# fpgaConfig.net
KiCad netlist of a schematic drawn in Altium Designer
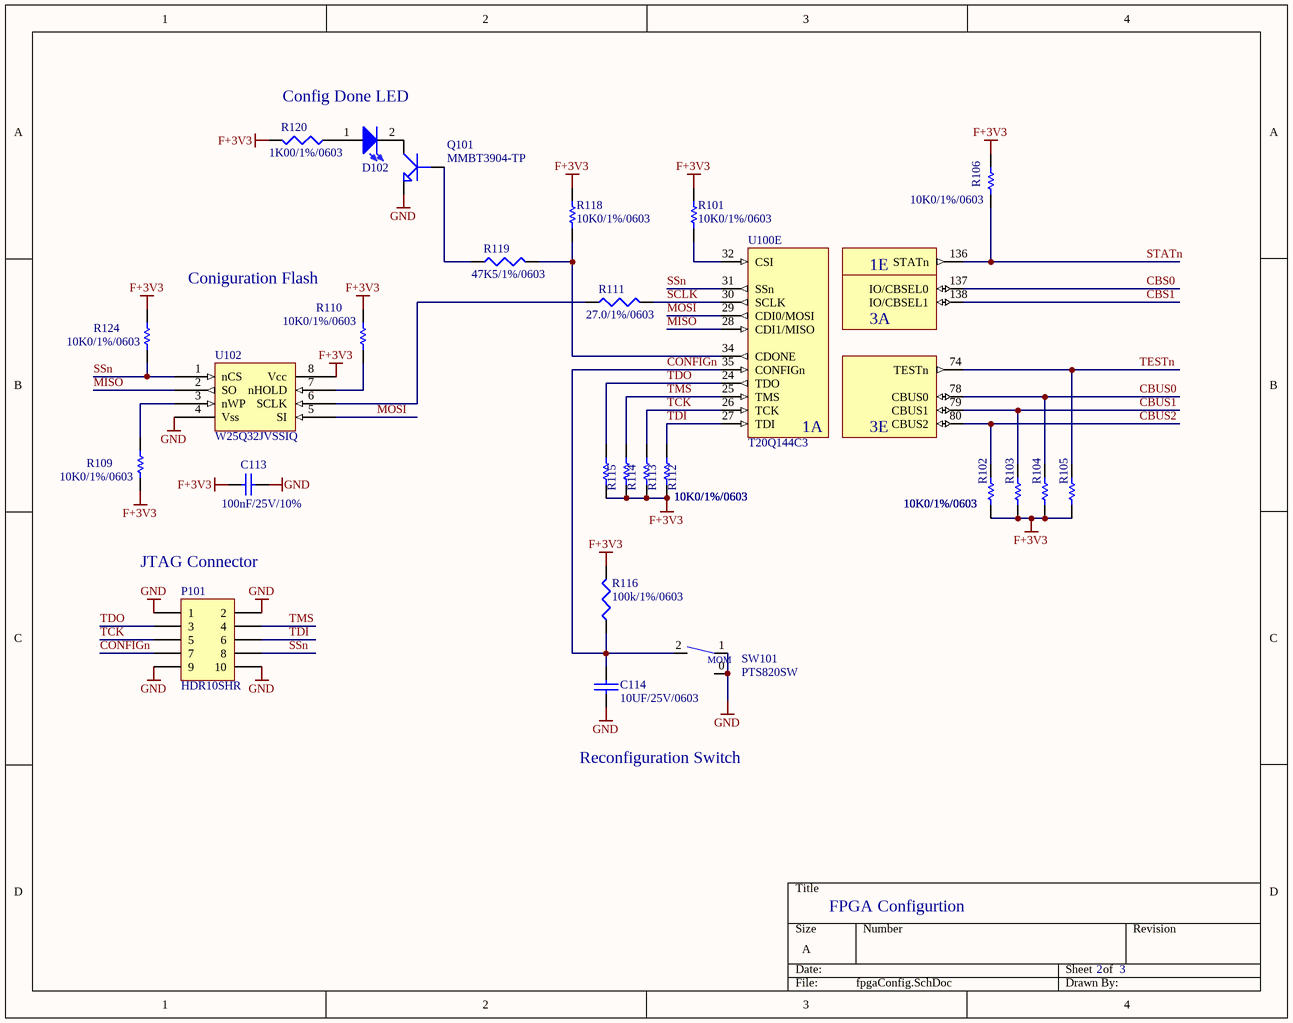
[diagram p0: fpgaConfig.SchDoc]

(export (version "E")
  (design (tool "Eeschema 10.0.6"))
  (components
    (comp (ref "C113")
      (value "100nF/25V/10%")
      (footprint "MY0603")
      (description "0.1µF ±10% 25V Ceramic Capacitor X7R 0603 (1608 Metric)")
      (fields (field (name "MFG") "AVX"))
      (libsource (lib "Capacitors") (part "CAP100NF25V"))
    )
    (comp (ref "C114")
      (value "10UF/25V/0603")
      (footprint "0603")
      (description "10 µF ±20% 25V Ceramic Capacitor X5R 0603 (1608 Metric)")
      (fields (field (name "MFG") "Samsung"))
      (libsource (lib "Capacitors") (part "10UF/25V/0603"))
    )
    (comp (ref "D102")
      (value "LTST-C191KGKT")
      (footprint "LED0603")
      (description "Green 571nm LED Indication - Discrete 2V 0603 (1608 Metric)")
      (fields (field (name "MFG") "Liteon"))
      (libsource (lib "MiscSemi") (part "LTST-C191KGKT"))
    )
    (comp (ref "P101")
      (value "HDR10SHR")
      (footprint "HDR10")
      (description "Connector Header Through Hole 10 position 0.100\" (2.54mm)")
      (fields (field (name "MFG") "On Shore"))
      (libsource (lib "Connectors") (part "HDR10SHR"))
    )
    (comp (ref "Q101")
      (value "MMBT3904-TP")
      (footprint "SOT-23")
      (description "Bipolar (BJT) Transistor NPN 40 V 200 mA 300MHz 350 mW Surface Mount SOT-23")
      (fields (field (name "MFG") "Micro Commercial"))
      (libsource (lib "MiscSemi") (part "MMBT3904-TP"))
    )
    (comp (ref "R101")
      (value "10K0/1%/0603")
      (footprint "0603")
      (description "10k Ohm ±1% 0.1W, 1/10W Chip Resistor 0603 (1608 Metric) Moisture Resistant Thick Film")
      (fields (field (name "MFG") "Yageo"))
      (libsource (lib "Resistors") (part "RES10K0"))
    )
    (comp (ref "R102")
      (value "10K0/1%/0603")
      (footprint "0603")
      (description "10k Ohm ±1% 0.1W, 1/10W Chip Resistor 0603 (1608 Metric) Moisture Resistant Thick Film")
      (fields (field (name "MFG") "Yageo"))
      (libsource (lib "Resistors") (part "RES10K0"))
    )
    (comp (ref "R103")
      (value "10K0/1%/0603")
      (footprint "0603")
      (description "10k Ohm ±1% 0.1W, 1/10W Chip Resistor 0603 (1608 Metric) Moisture Resistant Thick Film")
      (fields (field (name "MFG") "Yageo"))
      (libsource (lib "Resistors") (part "RES10K0"))
    )
    (comp (ref "R104")
      (value "10K0/1%/0603")
      (footprint "0603")
      (description "10k Ohm ±1% 0.1W, 1/10W Chip Resistor 0603 (1608 Metric) Moisture Resistant Thick Film")
      (fields (field (name "MFG") "Yageo"))
      (libsource (lib "Resistors") (part "RES10K0"))
    )
    (comp (ref "R105")
      (value "10K0/1%/0603")
      (footprint "0603")
      (description "10k Ohm ±1% 0.1W, 1/10W Chip Resistor 0603 (1608 Metric) Moisture Resistant Thick Film")
      (fields (field (name "MFG") "Yageo"))
      (libsource (lib "Resistors") (part "RES10K0"))
    )
    (comp (ref "R106")
      (value "10K0/1%/0603")
      (footprint "0603")
      (description "10k Ohm ±1% 0.1W, 1/10W Chip Resistor 0603 (1608 Metric) Moisture Resistant Thick Film")
      (fields (field (name "MFG") "Yageo"))
      (libsource (lib "Resistors") (part "RES10K0"))
    )
    (comp (ref "R109")
      (value "10K0/1%/0603")
      (footprint "0603")
      (description "10k Ohm ±1% 0.1W, 1/10W Chip Resistor 0603 (1608 Metric) Moisture Resistant Thick Film")
      (fields (field (name "MFG") "Yageo"))
      (libsource (lib "Resistors") (part "RES10K0"))
    )
    (comp (ref "R110")
      (value "10K0/1%/0603")
      (footprint "0603")
      (description "10k Ohm ±1% 0.1W, 1/10W Chip Resistor 0603 (1608 Metric) Moisture Resistant Thick Film")
      (fields (field (name "MFG") "Yageo"))
      (libsource (lib "Resistors") (part "RES10K0"))
    )
    (comp (ref "R111")
      (value "27.0/1%/0603")
      (footprint "0603")
      (description "27 Ohms ±1% 0.1W, 1/10W Chip Resistor 0603 (1608 Metric) Moisture Resistant Thick Film")
      (fields (field (name "MFG") "Yeago"))
      (libsource (lib "Resistors") (part "27.0/1%/0603"))
    )
    (comp (ref "R112")
      (value "10K0/1%/0603")
      (footprint "0603")
      (description "10k Ohm ±1% 0.1W, 1/10W Chip Resistor 0603 (1608 Metric) Moisture Resistant Thick Film")
      (fields (field (name "MFG") "Yageo"))
      (libsource (lib "Resistors") (part "RES10K0"))
    )
    (comp (ref "R113")
      (value "10K0/1%/0603")
      (footprint "0603")
      (description "10k Ohm ±1% 0.1W, 1/10W Chip Resistor 0603 (1608 Metric) Moisture Resistant Thick Film")
      (fields (field (name "MFG") "Yageo"))
      (libsource (lib "Resistors") (part "RES10K0"))
    )
    (comp (ref "R114")
      (value "10K0/1%/0603")
      (footprint "0603")
      (description "10k Ohm ±1% 0.1W, 1/10W Chip Resistor 0603 (1608 Metric) Moisture Resistant Thick Film")
      (fields (field (name "MFG") "Yageo"))
      (libsource (lib "Resistors") (part "RES10K0"))
    )
    (comp (ref "R115")
      (value "10K0/1%/0603")
      (footprint "0603")
      (description "10k Ohm ±1% 0.1W, 1/10W Chip Resistor 0603 (1608 Metric) Moisture Resistant Thick Film")
      (fields (field (name "MFG") "Yageo"))
      (libsource (lib "Resistors") (part "RES10K0"))
    )
    (comp (ref "R116")
      (value "100k/1%/0603")
      (footprint "0603")
      (description "100 kOhms ±1% 0.1W, 1/10W Chip Resistor 0603 (1608 Metric) Moisture Resistant Thick Film")
      (fields (field (name "MFG") "Yeago"))
      (libsource (lib "Resistors") (part "100k/1%/0603"))
    )
    (comp (ref "R118")
      (value "10K0/1%/0603")
      (footprint "0603")
      (description "10k Ohm ±1% 0.1W, 1/10W Chip Resistor 0603 (1608 Metric) Moisture Resistant Thick Film")
      (fields (field (name "MFG") "Yageo"))
      (libsource (lib "Resistors") (part "RES10K0"))
    )
    (comp (ref "R119")
      (value "47K5/1%/0603")
      (footprint "0603")
      (description "47.5 kOhms ±1% 0.1W, 1/10W Chip Resistor 0603 (1608 Metric) Moisture Resistant Thick Film")
      (fields (field (name "MFG") "Yeago"))
      (libsource (lib "Resistors") (part "47K5/1%/0603"))
    )
    (comp (ref "R120")
      (value "1K00/1%/0603")
      (footprint "0603")
      (description "1 kOhms ±1% 0.1W, 1/10W Chip Resistor 0603 (1608 Metric) Moisture Resistant Thick Film")
      (fields (field (name "MFG") "Yeago"))
      (libsource (lib "Resistors") (part "1K00/1%/0603"))
    )
    (comp (ref "R124")
      (value "10K0/1%/0603")
      (footprint "0603")
      (description "10k Ohm ±1% 0.1W, 1/10W Chip Resistor 0603 (1608 Metric) Moisture Resistant Thick Film")
      (fields (field (name "MFG") "Yageo"))
      (libsource (lib "Resistors") (part "RES10K0"))
    )
    (comp (ref "SW101")
      (value "PTS820SW")
      (footprint "PTS820")
      (description "Tactile Switch SPST-NO Top Actuated Surface Mount")
      (fields (field (name "MFG") "C&K"))
      (libsource (lib "Misc") (part "PTS820SW"))
    )
    (comp (ref "U100")
      (value "T20Q144C3")
      (footprint "LQFP144")
      (description "Trion® Field Programmable Gate Array (FPGA) IC 97 1044 19728 144-LQFP")
      (fields (field (name "MFG") "Efinix"))
      (libsource (lib "DigitalIC") (part "T20Q144C3"))
    )
    (comp (ref "U102")
      (value "W25Q32JVSSIQ")
      (footprint "so8w")
      (description "FLASH - NOR Memory IC 32Mb (4M x 8) SPI - Quad I/O 133 MHz 8-SOIC")
      (fields (field (name "MFG") "Winbond"))
      (libsource (lib "DigitalIC") (part "W25Q32JVSSIQ"))
    )
  )
  (nets
    (net (code "1") (name "/CBS0") (class "Default")
      (node (ref "U100") (pin "137") (pinfunction "IO/CBSEL0_137") (pintype "bidirectional"))
    )
    (net (code "2") (name "/CBS1") (class "Default")
      (node (ref "U100") (pin "138") (pinfunction "IO/CBSEL1_138") (pintype "bidirectional"))
    )
    (net (code "3") (name "/CBUS0") (class "Default")
      (node (ref "R104") (pin "2") (pinfunction "2_2") (pintype "passive"))
      (node (ref "U100") (pin "78") (pinfunction "CBUS0_78") (pintype "bidirectional"))
    )
    (net (code "4") (name "/CBUS1") (class "Default")
      (node (ref "R103") (pin "2") (pinfunction "2_2") (pintype "passive"))
      (node (ref "U100") (pin "79") (pinfunction "CBUS1_79") (pintype "bidirectional"))
    )
    (net (code "5") (name "/CBUS2") (class "Default")
      (node (ref "R102") (pin "2") (pinfunction "2_2") (pintype "passive"))
      (node (ref "U100") (pin "80") (pinfunction "CBUS2_80") (pintype "bidirectional"))
    )
    (net (code "6") (name "/CONFIGn") (class "Default")
      (node (ref "C114") (pin "1") (pintype "passive"))
      (node (ref "P101") (pin "7") (pinfunction "7_7") (pintype "passive"))
      (node (ref "R116") (pin "1") (pintype "passive"))
      (node (ref "SW101") (pin "2") (pinfunction "2_2") (pintype "passive"))
      (node (ref "U100") (pin "35") (pinfunction "CONFIGn_35") (pintype "input"))
    )
    (net (code "7") (name "/MISO") (class "Default")
      (node (ref "U100") (pin "28") (pinfunction "CDI1/MISO_28") (pintype "input"))
      (node (ref "U102") (pin "2") (pinfunction "SO_2") (pintype "output"))
    )
    (net (code "8") (name "/MOSI") (class "Default")
      (node (ref "U100") (pin "29") (pinfunction "CDI0/MOSI_29") (pintype "output"))
      (node (ref "U102") (pin "5") (pinfunction "SI_5") (pintype "input"))
    )
    (net (code "9") (name "/SCLK") (class "Default")
      (node (ref "R111") (pin "2") (pintype "passive"))
      (node (ref "U100") (pin "30") (pinfunction "SCLK_30") (pintype "output"))
    )
    (net (code "10") (name "/SSn") (class "Default")
      (node (ref "P101") (pin "8") (pinfunction "8_8") (pintype "passive"))
      (node (ref "R124") (pin "1") (pinfunction "1_1") (pintype "passive"))
      (node (ref "U100") (pin "31") (pinfunction "SSn_31") (pintype "output"))
      (node (ref "U102") (pin "1") (pinfunction "nCS_1") (pintype "input"))
    )
    (net (code "11") (name "/STATn") (class "Default")
      (node (ref "R106") (pin "1") (pinfunction "1_1") (pintype "passive"))
      (node (ref "U100") (pin "136") (pinfunction "STATn_136") (pintype "output"))
    )
    (net (code "12") (name "/TCK") (class "Default")
      (node (ref "P101") (pin "5") (pinfunction "5_5") (pintype "passive"))
      (node (ref "R113") (pin "2") (pinfunction "2_2") (pintype "passive"))
      (node (ref "U100") (pin "26") (pinfunction "TCK_26") (pintype "input"))
    )
    (net (code "13") (name "/TDI") (class "Default")
      (node (ref "P101") (pin "6") (pinfunction "6_6") (pintype "passive"))
      (node (ref "R112") (pin "2") (pinfunction "2_2") (pintype "passive"))
      (node (ref "U100") (pin "27") (pinfunction "TDI_27") (pintype "input"))
    )
    (net (code "14") (name "/TDO") (class "Default")
      (node (ref "P101") (pin "3") (pinfunction "3_3") (pintype "passive"))
      (node (ref "R115") (pin "2") (pinfunction "2_2") (pintype "passive"))
      (node (ref "U100") (pin "24") (pinfunction "TDO_24") (pintype "output"))
    )
    (net (code "15") (name "/TESTn") (class "Default")
      (node (ref "R105") (pin "2") (pinfunction "2_2") (pintype "passive"))
      (node (ref "U100") (pin "74") (pinfunction "TESTn_74") (pintype "output"))
    )
    (net (code "16") (name "/TMS") (class "Default")
      (node (ref "P101") (pin "4") (pinfunction "4_4") (pintype "passive"))
      (node (ref "R114") (pin "2") (pinfunction "2_2") (pintype "passive"))
      (node (ref "U100") (pin "25") (pinfunction "TMS_25") (pintype "input"))
    )
    (net (code "17") (name "F+3V3") (class "Default")
      (node (ref "C113") (pin "2") (pinfunction "2_2") (pintype "passive"))
      (node (ref "R101") (pin "2") (pinfunction "2_2") (pintype "passive"))
      (node (ref "R102") (pin "1") (pinfunction "1_1") (pintype "passive"))
      (node (ref "R103") (pin "1") (pinfunction "1_1") (pintype "passive"))
      (node (ref "R104") (pin "1") (pinfunction "1_1") (pintype "passive"))
      (node (ref "R105") (pin "1") (pinfunction "1_1") (pintype "passive"))
      (node (ref "R106") (pin "2") (pinfunction "2_2") (pintype "passive"))
      (node (ref "R109") (pin "1") (pinfunction "1_1") (pintype "passive"))
      (node (ref "R110") (pin "1") (pinfunction "1_1") (pintype "passive"))
      (node (ref "R112") (pin "1") (pinfunction "1_1") (pintype "passive"))
      (node (ref "R113") (pin "1") (pinfunction "1_1") (pintype "passive"))
      (node (ref "R114") (pin "1") (pinfunction "1_1") (pintype "passive"))
      (node (ref "R115") (pin "1") (pinfunction "1_1") (pintype "passive"))
      (node (ref "R116") (pin "2") (pintype "passive"))
      (node (ref "R118") (pin "2") (pinfunction "2_2") (pintype "passive"))
      (node (ref "R120") (pin "2") (pintype "passive"))
      (node (ref "R124") (pin "2") (pinfunction "2_2") (pintype "passive"))
      (node (ref "U102") (pin "8") (pinfunction "Vcc_8") (pintype "power_in"))
    )
    (net (code "18") (name "GND") (class "Default")
      (node (ref "C113") (pin "1") (pinfunction "1_1") (pintype "passive"))
      (node (ref "C114") (pin "2") (pintype "passive"))
      (node (ref "P101") (pin "1") (pinfunction "1_1") (pintype "passive"))
      (node (ref "P101") (pin "10") (pinfunction "10_10") (pintype "passive"))
      (node (ref "P101") (pin "2") (pinfunction "2_2") (pintype "passive"))
      (node (ref "P101") (pin "9") (pinfunction "9_9") (pintype "passive"))
      (node (ref "Q101") (pin "2") (pinfunction "EMITTER_2") (pintype "passive"))
      (node (ref "SW101") (pin "0") (pinfunction "0_0") (pintype "passive"))
      (node (ref "SW101") (pin "1") (pinfunction "1_1") (pintype "passive"))
      (node (ref "U102") (pin "4") (pinfunction "Vss_4") (pintype "power_in"))
    )
    (net (code "19") (name "Net-(D102-A)") (class "Default")
      (node (ref "D102") (pin "1") (pinfunction "A_1") (pintype "passive"))
      (node (ref "R120") (pin "1") (pintype "passive"))
    )
    (net (code "20") (name "Net-(D102-K)") (class "Default")
      (node (ref "D102") (pin "2") (pinfunction "K_2") (pintype "passive"))
      (node (ref "Q101") (pin "3") (pinfunction "COLLECTOR_3") (pintype "passive"))
    )
    (net (code "21") (name "Net-(Q101-BASE)") (class "Default")
      (node (ref "Q101") (pin "1") (pinfunction "BASE_1") (pintype "power_in"))
      (node (ref "R119") (pin "1") (pintype "passive"))
    )
    (net (code "22") (name "Net-(U100E-CDONE)") (class "Default")
      (node (ref "R118") (pin "1") (pinfunction "1_1") (pintype "passive"))
      (node (ref "R119") (pin "2") (pintype "passive"))
      (node (ref "U100") (pin "34") (pinfunction "CDONE_34") (pintype "output"))
    )
    (net (code "23") (name "Net-(U100E-CSI)") (class "Default")
      (node (ref "R101") (pin "1") (pinfunction "1_1") (pintype "passive"))
      (node (ref "U100") (pin "32") (pinfunction "CSI_32") (pintype "input"))
    )
    (net (code "24") (name "Net-(U102-SCLK)") (class "Default")
      (node (ref "R111") (pin "1") (pintype "passive"))
      (node (ref "U102") (pin "6") (pinfunction "SCLK_6") (pintype "input"))
    )
    (net (code "25") (name "Net-(U102-nHOLD)") (class "Default")
      (node (ref "R110") (pin "2") (pinfunction "2_2") (pintype "passive"))
      (node (ref "U102") (pin "7") (pinfunction "nHOLD_7") (pintype "input"))
    )
    (net (code "26") (name "Net-(U102-nWP)") (class "Default")
      (node (ref "R109") (pin "2") (pinfunction "2_2") (pintype "passive"))
      (node (ref "U102") (pin "3") (pinfunction "nWP_3") (pintype "input"))
    )
  )
)
